# S7G2_footprint_with_caps_v1p1.net
KiCad netlist of a schematic drawn in EAGLE
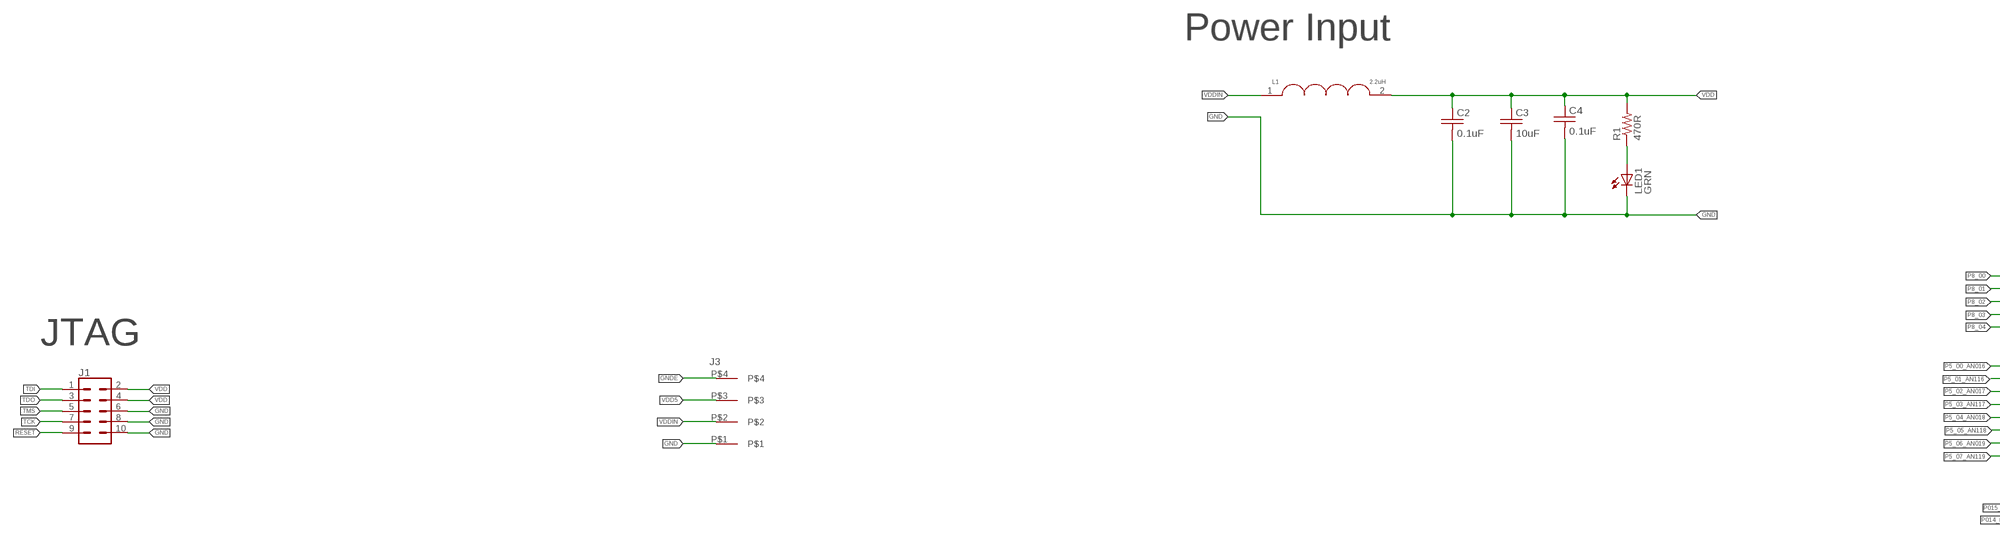
[diagram p0: schematic, sheet 1, part 1 of 3]
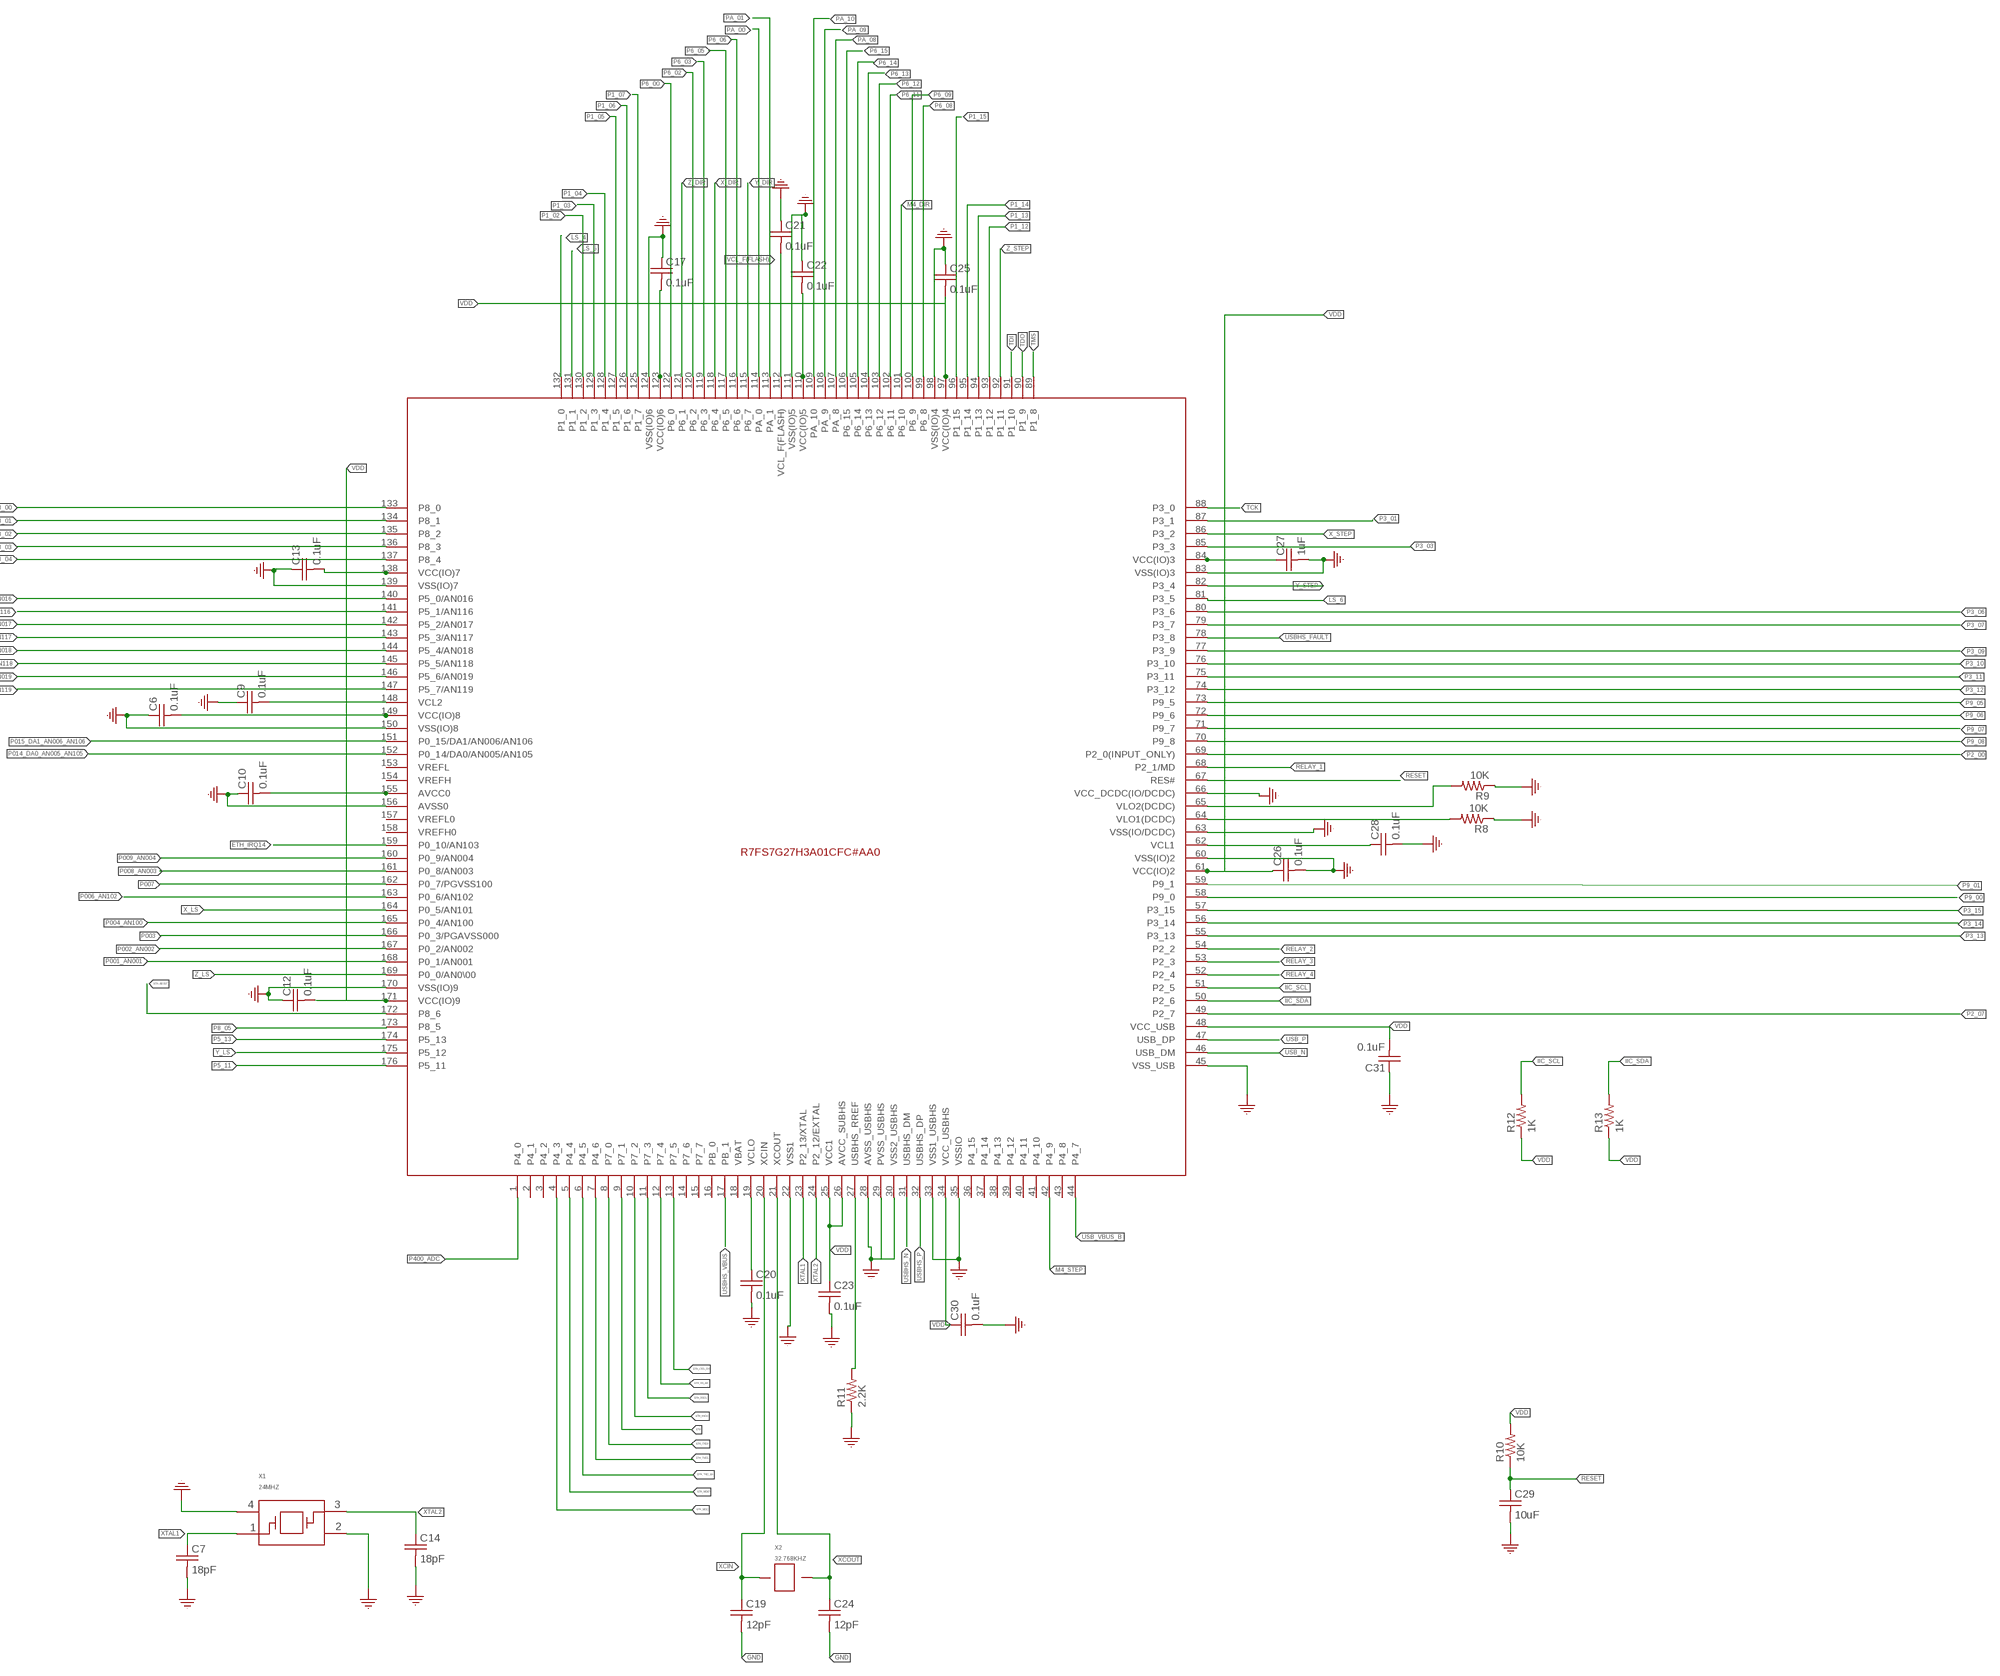
[diagram p1: schematic, sheet 1, part 2 of 3]
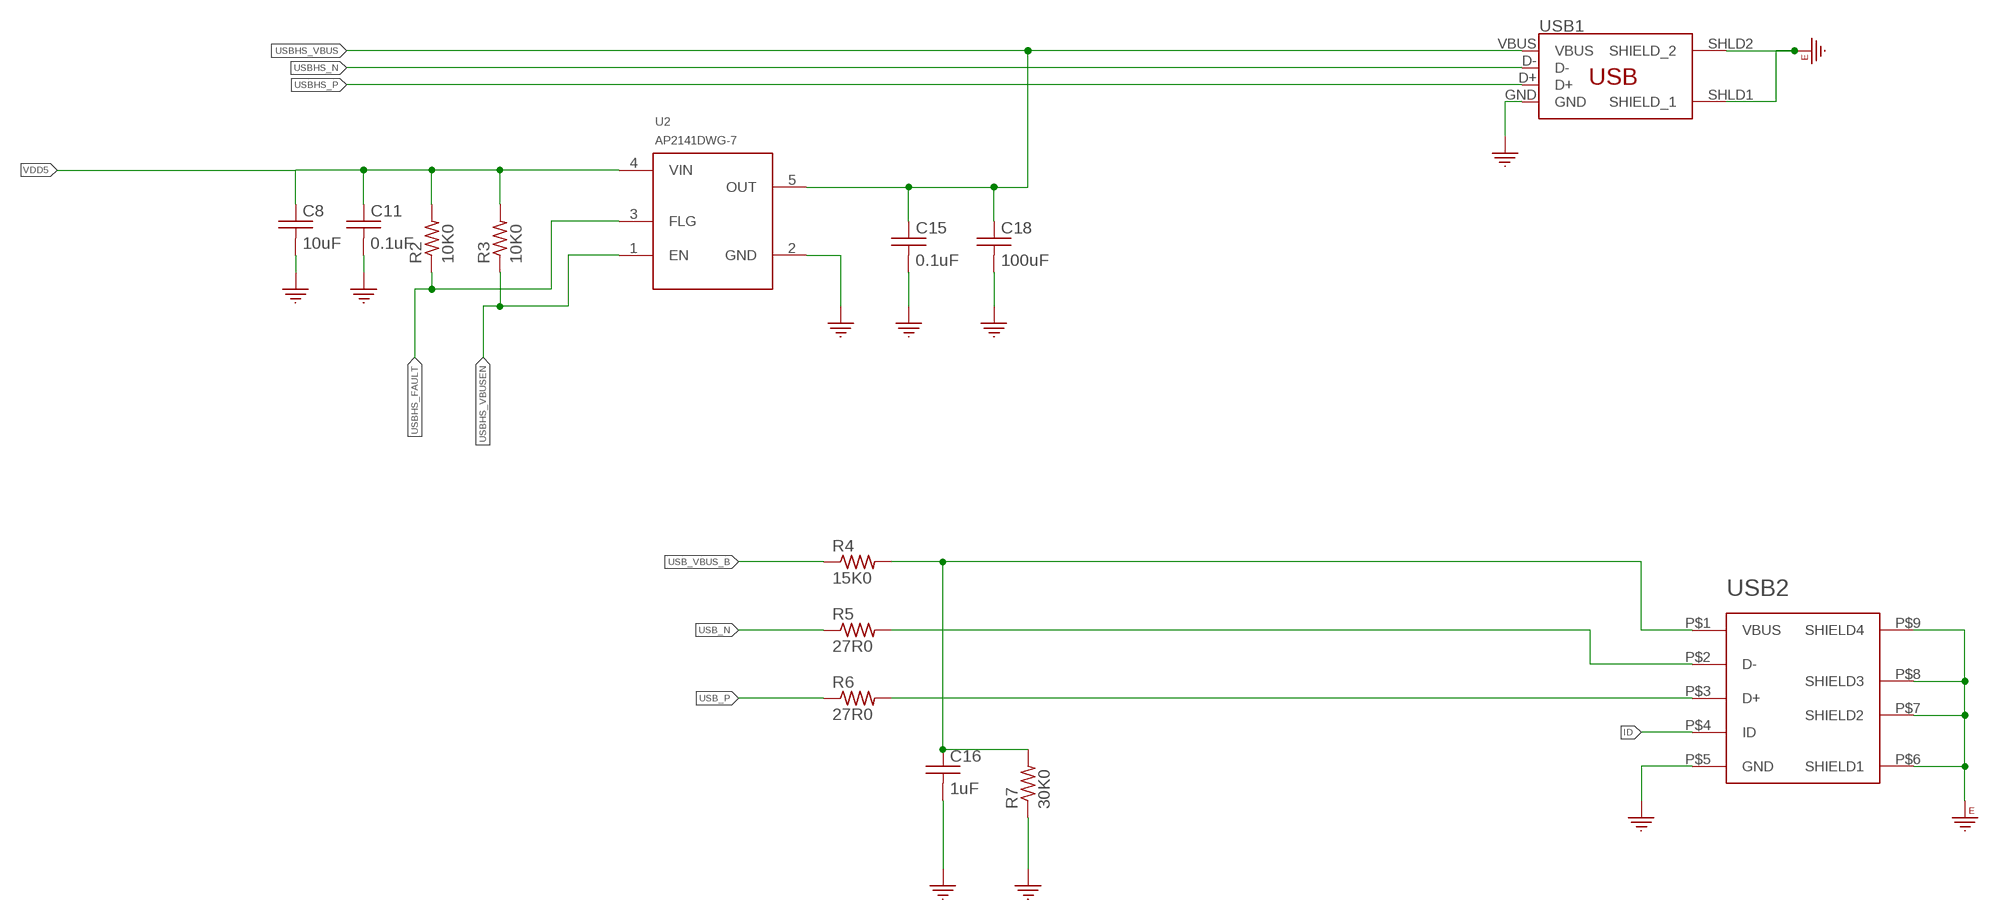
[diagram p2: schematic, sheet 1, part 3 of 3]

(export (version "E")
  (design (tool "Eeschema 10.0.6"))
  (components
    (comp (ref "C2")
      (value "0.1uF")
      (footprint "eagle-import:0402")
      (libsource (lib "eagle-import") (part "C_0402"))
    )
    (comp (ref "C3")
      (value "10uF")
      (footprint "eagle-import:0402")
      (libsource (lib "eagle-import") (part "C_0402"))
    )
    (comp (ref "C4")
      (value "0.1uF")
      (footprint "eagle-import:0402")
      (libsource (lib "eagle-import") (part "C_0402"))
    )
    (comp (ref "C6")
      (value "0.1uF")
      (footprint "eagle-import:0402")
      (libsource (lib "eagle-import") (part "C_0402"))
    )
    (comp (ref "C7")
      (value "18pF")
      (footprint "eagle-import:0402")
      (libsource (lib "eagle-import") (part "C_0402"))
    )
    (comp (ref "C8")
      (value "10uF")
      (footprint "eagle-import:0402")
      (libsource (lib "eagle-import") (part "C_0402"))
    )
    (comp (ref "C9")
      (value "0.1uF")
      (footprint "eagle-import:0402")
      (libsource (lib "eagle-import") (part "C_0402"))
    )
    (comp (ref "C10")
      (value "0.1uF")
      (footprint "eagle-import:0402")
      (libsource (lib "eagle-import") (part "C_0402"))
    )
    (comp (ref "C11")
      (value "0.1uF")
      (footprint "eagle-import:0402")
      (libsource (lib "eagle-import") (part "C_0402"))
    )
    (comp (ref "C12")
      (value "0.1uF")
      (footprint "eagle-import:0402")
      (libsource (lib "eagle-import") (part "C_0402"))
    )
    (comp (ref "C13")
      (value "0.1uF")
      (footprint "eagle-import:0402")
      (libsource (lib "eagle-import") (part "C_0402"))
    )
    (comp (ref "C14")
      (value "18pF")
      (footprint "eagle-import:0402")
      (libsource (lib "eagle-import") (part "C_0402"))
    )
    (comp (ref "C15")
      (value "0.1uF")
      (footprint "eagle-import:0402")
      (libsource (lib "eagle-import") (part "C_0402"))
    )
    (comp (ref "C16")
      (value "1uF")
      (footprint "eagle-import:0402")
      (libsource (lib "eagle-import") (part "C_0402"))
    )
    (comp (ref "C17")
      (value "0.1uF")
      (footprint "eagle-import:0402")
      (libsource (lib "eagle-import") (part "C_0402"))
    )
    (comp (ref "C18")
      (value "100uF")
      (footprint "eagle-import:C1210")
      (libsource (lib "eagle-import") (part "C_1210"))
    )
    (comp (ref "C19")
      (value "12pF")
      (footprint "eagle-import:0402")
      (libsource (lib "eagle-import") (part "C_0402"))
    )
    (comp (ref "C20")
      (value "0.1uF")
      (footprint "eagle-import:0402")
      (libsource (lib "eagle-import") (part "C_0402"))
    )
    (comp (ref "C21")
      (value "0.1uF")
      (footprint "eagle-import:0402")
      (libsource (lib "eagle-import") (part "C_0402"))
    )
    (comp (ref "C22")
      (value "0.1uF")
      (footprint "eagle-import:0402")
      (libsource (lib "eagle-import") (part "C_0402"))
    )
    (comp (ref "C23")
      (value "0.1uF")
      (footprint "eagle-import:0402")
      (libsource (lib "eagle-import") (part "C_0402"))
    )
    (comp (ref "C24")
      (value "12pF")
      (footprint "eagle-import:0402")
      (libsource (lib "eagle-import") (part "C_0402"))
    )
    (comp (ref "C25")
      (value "0.1uF")
      (footprint "eagle-import:0402")
      (libsource (lib "eagle-import") (part "C_0402"))
    )
    (comp (ref "C26")
      (value "0.1uF")
      (footprint "eagle-import:0402")
      (libsource (lib "eagle-import") (part "C_0402"))
    )
    (comp (ref "C27")
      (value "1uF")
      (footprint "eagle-import:0402")
      (libsource (lib "eagle-import") (part "C_0402"))
    )
    (comp (ref "C28")
      (value "0.1uF")
      (footprint "eagle-import:0402")
      (libsource (lib "eagle-import") (part "C_0402"))
    )
    (comp (ref "C29")
      (value "10uF")
      (footprint "eagle-import:0402")
      (libsource (lib "eagle-import") (part "C_0402"))
    )
    (comp (ref "C30")
      (value "0.1uF")
      (footprint "eagle-import:0402")
      (libsource (lib "eagle-import") (part "C_0402"))
    )
    (comp (ref "C31")
      (value "0.1uF")
      (footprint "eagle-import:0402")
      (libsource (lib "eagle-import") (part "C_0402"))
    )
    (comp (ref "J1")
      (value "CONN_05X2PTH")
      (footprint "eagle-import:2X5")
      (libsource (lib "eagle-import") (part "CONN_05X2PTH"))
    )
    (comp (ref "J3")
      (value "3.81MM_1_X_4_RT_ANGLE_PLUG_HEADER")
      (footprint "eagle-import:1X4_3.81MM_PITCH")
      (libsource (lib "eagle-import") (part "3.81MM_1_X_4_RT_ANGLE_PLUG_HEADER"))
    )
    (comp (ref "L1")
      (value "2.2uH")
      (footprint "eagle-import:1008_(2520_METRIC)")
      (libsource (lib "eagle-import") (part "INDUCTOR_1008_2.2_MH_1.3A"))
    )
    (comp (ref "LED1")
      (value "LED_0805_GREEN")
      (footprint "eagle-import:LED_0805_GREEN")
      (libsource (lib "eagle-import") (part "LED_0805_GREEN"))
    )
    (comp (ref "R1")
      (value "470R")
      (footprint "eagle-import:0402")
      (libsource (lib "eagle-import") (part "R_0402"))
    )
    (comp (ref "R2")
      (value "10K0")
      (footprint "eagle-import:0402")
      (libsource (lib "eagle-import") (part "R_0402"))
    )
    (comp (ref "R3")
      (value "10K0")
      (footprint "eagle-import:0402")
      (libsource (lib "eagle-import") (part "R_0402"))
    )
    (comp (ref "R4")
      (value "15K0")
      (footprint "eagle-import:0402")
      (libsource (lib "eagle-import") (part "R_0402"))
    )
    (comp (ref "R5")
      (value "27R0")
      (footprint "eagle-import:0402")
      (libsource (lib "eagle-import") (part "R_0402"))
    )
    (comp (ref "R6")
      (value "27R0")
      (footprint "eagle-import:0402")
      (libsource (lib "eagle-import") (part "R_0402"))
    )
    (comp (ref "R7")
      (value "30K0")
      (footprint "eagle-import:0402")
      (libsource (lib "eagle-import") (part "R_0402"))
    )
    (comp (ref "R8")
      (value "10K")
      (footprint "eagle-import:0402")
      (libsource (lib "eagle-import") (part "R_0402"))
    )
    (comp (ref "R9")
      (value "10K")
      (footprint "eagle-import:0402")
      (libsource (lib "eagle-import") (part "R_0402"))
    )
    (comp (ref "R10")
      (value "10K")
      (footprint "eagle-import:0402")
      (libsource (lib "eagle-import") (part "R_0402"))
    )
    (comp (ref "R11")
      (value "2.2K")
      (footprint "eagle-import:0402")
      (libsource (lib "eagle-import") (part "R_0402"))
    )
    (comp (ref "R12")
      (value "1K")
      (footprint "eagle-import:0402")
      (libsource (lib "eagle-import") (part "R_0402"))
    )
    (comp (ref "R13")
      (value "1K")
      (footprint "eagle-import:0402")
      (libsource (lib "eagle-import") (part "R_0402"))
    )
    (comp (ref "U2")
      (value "AP2141DWG-5")
      (footprint "eagle-import:SOT-23-5")
      (libsource (lib "eagle-import") (part "AP2141DWG-5"))
    )
    (comp (ref "U5")
      (value "S7G2_X_176")
      (footprint "eagle-import:LQFP176_24X24")
      (libsource (lib "eagle-import") (part "S7G2_X_176"))
    )
    (comp (ref "USB1")
      (value "USB_A")
      (footprint "eagle-import:USB_A_SMT")
      (libsource (lib "eagle-import") (part "USB_A"))
    )
    (comp (ref "USB2")
      (value "USB_MICRO-B")
      (footprint "eagle-import:USB_MICRO-B")
      (libsource (lib "eagle-import") (part "USB_MICRO-B"))
    )
    (comp (ref "X1")
      (value "24MHZ")
      (footprint "eagle-import:SMD_3225")
      (libsource (lib "eagle-import") (part "XTAL_24_MHZ"))
    )
    (comp (ref "X2")
      (value "32.768KHZ")
      (footprint "eagle-import:SMD_X_2_PADS")
      (libsource (lib "eagle-import") (part "XTAL_32.768KHZ"))
    )
  )
  (nets
    (net (code "1") (name "ETH") (class "Default")
      (node (ref "U5") (pin "9") (pinfunction "P7_1_9") (pintype "bidirectional"))
    )
    (net (code "2") (name "ETH_CRS_DV") (class "Default")
      (node (ref "U5") (pin "13") (pinfunction "P7_5_13") (pintype "bidirectional"))
    )
    (net (code "3") (name "ETH_IRQ14") (class "Default")
      (node (ref "U5") (pin "159") (pinfunction "P0_10/AN103_159") (pintype "bidirectional"))
    )
    (net (code "4") (name "ETH_MDC") (class "Default")
      (node (ref "U5") (pin "4") (pinfunction "P4_3_4") (pintype "bidirectional"))
    )
    (net (code "5") (name "ETH_MDIO") (class "Default")
      (node (ref "U5") (pin "5") (pinfunction "P4_4_5") (pintype "bidirectional"))
    )
    (net (code "6") (name "ETH_RESET") (class "Default")
      (node (ref "U5") (pin "172") (pinfunction "P8_6_172") (pintype "bidirectional"))
    )
    (net (code "7") (name "ETH_RXD0") (class "Default")
      (node (ref "U5") (pin "10") (pinfunction "P7_2_10") (pintype "bidirectional"))
    )
    (net (code "8") (name "ETH_RXD1") (class "Default")
      (node (ref "U5") (pin "11") (pinfunction "P7_3_11") (pintype "bidirectional"))
    )
    (net (code "9") (name "ETH_RX_ER") (class "Default")
      (node (ref "U5") (pin "12") (pinfunction "P7_4_12") (pintype "bidirectional"))
    )
    (net (code "10") (name "ETH_TXD0") (class "Default")
      (node (ref "U5") (pin "8") (pinfunction "P7_0_8") (pintype "bidirectional"))
    )
    (net (code "11") (name "ETH_TXD1") (class "Default")
      (node (ref "U5") (pin "7") (pinfunction "P4_6_7") (pintype "bidirectional"))
    )
    (net (code "12") (name "ETH_TXD_EN") (class "Default")
      (node (ref "U5") (pin "6") (pinfunction "P4_5_6") (pintype "bidirectional"))
    )
    (net (code "13") (name "GND") (class "Default")
      (node (ref "C10") (pin "P$1") (pinfunction "1_P$1") (pintype "passive"))
      (node (ref "C11") (pin "P$2") (pinfunction "2_P$2") (pintype "passive"))
      (node (ref "C12") (pin "P$1") (pinfunction "1_P$1") (pintype "passive"))
      (node (ref "C13") (pin "P$1") (pinfunction "1_P$1") (pintype "passive"))
      (node (ref "C14") (pin "P$2") (pinfunction "2_P$2") (pintype "passive"))
      (node (ref "C15") (pin "P$2") (pinfunction "2_P$2") (pintype "passive"))
      (node (ref "C16") (pin "P$2") (pinfunction "2_P$2") (pintype "passive"))
      (node (ref "C17") (pin "P$1") (pinfunction "1_P$1") (pintype "passive"))
      (node (ref "C18") (pin "2") (pinfunction "2_2") (pintype "passive"))
      (node (ref "C19") (pin "P$2") (pinfunction "2_P$2") (pintype "passive"))
      (node (ref "C2") (pin "P$2") (pinfunction "2_P$2") (pintype "passive"))
      (node (ref "C20") (pin "P$2") (pinfunction "2_P$2") (pintype "passive"))
      (node (ref "C21") (pin "P$1") (pinfunction "1_P$1") (pintype "passive"))
      (node (ref "C22") (pin "P$1") (pinfunction "1_P$1") (pintype "passive"))
      (node (ref "C23") (pin "P$2") (pinfunction "2_P$2") (pintype "passive"))
      (node (ref "C24") (pin "P$2") (pinfunction "2_P$2") (pintype "passive"))
      (node (ref "C25") (pin "P$1") (pinfunction "1_P$1") (pintype "passive"))
      (node (ref "C26") (pin "P$2") (pinfunction "2_P$2") (pintype "passive"))
      (node (ref "C27") (pin "P$2") (pinfunction "2_P$2") (pintype "passive"))
      (node (ref "C28") (pin "P$2") (pinfunction "2_P$2") (pintype "passive"))
      (node (ref "C29") (pin "P$2") (pinfunction "2_P$2") (pintype "passive"))
      (node (ref "C3") (pin "P$2") (pinfunction "2_P$2") (pintype "passive"))
      (node (ref "C30") (pin "P$2") (pinfunction "2_P$2") (pintype "passive"))
      (node (ref "C31") (pin "P$1") (pinfunction "1_P$1") (pintype "passive"))
      (node (ref "C4") (pin "P$2") (pinfunction "2_P$2") (pintype "passive"))
      (node (ref "C6") (pin "P$1") (pinfunction "1_P$1") (pintype "passive"))
      (node (ref "C7") (pin "P$2") (pinfunction "2_P$2") (pintype "passive"))
      (node (ref "C8") (pin "P$2") (pinfunction "2_P$2") (pintype "passive"))
      (node (ref "C9") (pin "P$1") (pinfunction "1_P$1") (pintype "passive"))
      (node (ref "J1") (pin "10") (pinfunction "10_10") (pintype "passive"))
      (node (ref "J1") (pin "6") (pinfunction "6_6") (pintype "passive"))
      (node (ref "J1") (pin "8") (pinfunction "8_8") (pintype "passive"))
      (node (ref "J3") (pin "P$1") (pinfunction "P$1_P$1") (pintype "bidirectional"))
      (node (ref "LED1") (pin "C") (pinfunction "C_C") (pintype "passive"))
      (node (ref "R11") (pin "P$1") (pinfunction "1_P$1") (pintype "passive"))
      (node (ref "R7") (pin "P$1") (pinfunction "1_P$1") (pintype "passive"))
      (node (ref "R8") (pin "P$1") (pinfunction "1_P$1") (pintype "passive"))
      (node (ref "R9") (pin "P$1") (pinfunction "1_P$1") (pintype "passive"))
      (node (ref "U2") (pin "2") (pinfunction "GND_2") (pintype "input"))
      (node (ref "U5") (pin "111") (pinfunction "VSS(IO)5_111") (pintype "bidirectional"))
      (node (ref "U5") (pin "124") (pinfunction "VSS(IO)6_124") (pintype "bidirectional"))
      (node (ref "U5") (pin "139") (pinfunction "VSS(IO)7_139") (pintype "bidirectional"))
      (node (ref "U5") (pin "150") (pinfunction "VSS(IO)8_150") (pintype "bidirectional"))
      (node (ref "U5") (pin "156") (pinfunction "AVSS0_156") (pintype "bidirectional"))
      (node (ref "U5") (pin "170") (pinfunction "VSS(IO)9_170") (pintype "bidirectional"))
      (node (ref "U5") (pin "22") (pinfunction "VSS1_22") (pintype "bidirectional"))
      (node (ref "U5") (pin "28") (pinfunction "AVSS_USBHS_28") (pintype "bidirectional"))
      (node (ref "U5") (pin "29") (pinfunction "PVSS_USBHS_29") (pintype "bidirectional"))
      (node (ref "U5") (pin "30") (pinfunction "VSS2_USBHS_30") (pintype "bidirectional"))
      (node (ref "U5") (pin "33") (pinfunction "VSS1_USBHS_33") (pintype "bidirectional"))
      (node (ref "U5") (pin "35") (pinfunction "VSSIO_35") (pintype "bidirectional"))
      (node (ref "U5") (pin "45") (pinfunction "VSS_USB_45") (pintype "bidirectional"))
      (node (ref "U5") (pin "60") (pinfunction "VSS(IO)2_60") (pintype "bidirectional"))
      (node (ref "U5") (pin "63") (pinfunction "VSS(IO/DCDC)_63") (pintype "bidirectional"))
      (node (ref "U5") (pin "66") (pinfunction "VCC_DCDC(IO/DCDC)_66") (pintype "bidirectional"))
      (node (ref "U5") (pin "83") (pinfunction "VSS(IO)3_83") (pintype "bidirectional"))
      (node (ref "U5") (pin "98") (pinfunction "VSS(IO)4_98") (pintype "bidirectional"))
      (node (ref "USB1") (pin "GND") (pinfunction "GND_GND") (pintype "power_in"))
      (node (ref "USB2") (pin "P$5") (pinfunction "GND_P$5") (pintype "bidirectional"))
      (node (ref "X1") (pin "2") (pinfunction "2_2") (pintype "bidirectional"))
      (node (ref "X1") (pin "4") (pinfunction "4_4") (pintype "bidirectional"))
    )
    (net (code "14") (name "GNDE") (class "Default")
      (node (ref "J3") (pin "P$4") (pinfunction "P$4_P$4") (pintype "bidirectional"))
      (node (ref "USB1") (pin "SHLD1") (pinfunction "SHIELD_1_SHLD1") (pintype "bidirectional"))
      (node (ref "USB1") (pin "SHLD2") (pinfunction "SHIELD_2_SHLD2") (pintype "bidirectional"))
      (node (ref "USB2") (pin "P$6") (pinfunction "SHIELD1_P$6") (pintype "bidirectional"))
      (node (ref "USB2") (pin "P$7") (pinfunction "SHIELD2_P$7") (pintype "bidirectional"))
      (node (ref "USB2") (pin "P$8") (pinfunction "SHIELD3_P$8") (pintype "bidirectional"))
      (node (ref "USB2") (pin "P$9") (pinfunction "SHIELD4_P$9") (pintype "bidirectional"))
    )
    (net (code "15") (name "ID") (class "Default")
      (node (ref "USB2") (pin "P$4") (pinfunction "ID_P$4") (pintype "bidirectional"))
    )
    (net (code "16") (name "IIC_SCL") (class "Default")
      (node (ref "R12") (pin "P$2") (pinfunction "2_P$2") (pintype "passive"))
      (node (ref "U5") (pin "51") (pinfunction "P2_5_51") (pintype "bidirectional"))
    )
    (net (code "17") (name "IIC_SDA") (class "Default")
      (node (ref "R13") (pin "P$2") (pinfunction "2_P$2") (pintype "passive"))
      (node (ref "U5") (pin "50") (pinfunction "P2_6_50") (pintype "bidirectional"))
    )
    (net (code "18") (name "LS_4") (class "Default")
      (node (ref "U5") (pin "132") (pinfunction "P1_0_132") (pintype "bidirectional"))
    )
    (net (code "19") (name "LS_5") (class "Default")
      (node (ref "U5") (pin "131") (pinfunction "P1_1_131") (pintype "bidirectional"))
    )
    (net (code "20") (name "LS_6") (class "Default")
      (node (ref "U5") (pin "81") (pinfunction "P3_5_81") (pintype "bidirectional"))
    )
    (net (code "21") (name "M4_DIR") (class "Default")
      (node (ref "U5") (pin "101") (pinfunction "P6_10_101") (pintype "bidirectional"))
    )
    (net (code "22") (name "M4_STEP") (class "Default")
      (node (ref "U5") (pin "42") (pinfunction "P4_9_42") (pintype "bidirectional"))
    )
    (net (code "23") (name "Net-(C9-2)") (class "Default")
      (node (ref "C9") (pin "P$2") (pinfunction "2_P$2") (pintype "passive"))
      (node (ref "U5") (pin "148") (pinfunction "VCL2_148") (pintype "bidirectional"))
    )
    (net (code "24") (name "Net-(C16-1)") (class "Default")
      (node (ref "C16") (pin "P$1") (pinfunction "1_P$1") (pintype "passive"))
      (node (ref "R4") (pin "P$2") (pinfunction "2_P$2") (pintype "passive"))
      (node (ref "R7") (pin "P$2") (pinfunction "2_P$2") (pintype "passive"))
      (node (ref "USB2") (pin "P$1") (pinfunction "VBUS_P$1") (pintype "bidirectional"))
    )
    (net (code "25") (name "Net-(C20-1)") (class "Default")
      (node (ref "C20") (pin "P$1") (pinfunction "1_P$1") (pintype "passive"))
      (node (ref "U5") (pin "19") (pinfunction "VCLO_19") (pintype "bidirectional"))
    )
    (net (code "26") (name "Net-(C28-1)") (class "Default")
      (node (ref "C28") (pin "P$1") (pinfunction "1_P$1") (pintype "passive"))
      (node (ref "U5") (pin "62") (pinfunction "VCL1_62") (pintype "bidirectional"))
    )
    (net (code "27") (name "Net-(R1-1)") (class "Default")
      (node (ref "LED1") (pin "A") (pinfunction "A_A") (pintype "passive"))
      (node (ref "R1") (pin "P$1") (pinfunction "1_P$1") (pintype "passive"))
    )
    (net (code "28") (name "Net-(R5-2)") (class "Default")
      (node (ref "R5") (pin "P$2") (pinfunction "2_P$2") (pintype "passive"))
      (node (ref "USB2") (pin "P$2") (pinfunction "D-_P$2") (pintype "bidirectional"))
    )
    (net (code "29") (name "Net-(R6-2)") (class "Default")
      (node (ref "R6") (pin "P$2") (pinfunction "2_P$2") (pintype "passive"))
      (node (ref "USB2") (pin "P$3") (pinfunction "D+_P$3") (pintype "bidirectional"))
    )
    (net (code "30") (name "Net-(R8-2)") (class "Default")
      (node (ref "R8") (pin "P$2") (pinfunction "2_P$2") (pintype "passive"))
      (node (ref "U5") (pin "64") (pinfunction "VLO1(DCDC)_64") (pintype "bidirectional"))
    )
    (net (code "31") (name "Net-(R9-2)") (class "Default")
      (node (ref "R9") (pin "P$2") (pinfunction "2_P$2") (pintype "passive"))
      (node (ref "U5") (pin "65") (pinfunction "VLO2(DCDC)_65") (pintype "bidirectional"))
    )
    (net (code "32") (name "Net-(R11-2)") (class "Default")
      (node (ref "R11") (pin "P$2") (pinfunction "2_P$2") (pintype "passive"))
      (node (ref "U5") (pin "27") (pinfunction "USBHS_RREF_27") (pintype "bidirectional"))
    )
    (net (code "33") (name "P1_02") (class "Default")
      (node (ref "U5") (pin "130") (pinfunction "P1_2_130") (pintype "bidirectional"))
    )
    (net (code "34") (name "P1_03") (class "Default")
      (node (ref "U5") (pin "129") (pinfunction "P1_3_129") (pintype "bidirectional"))
    )
    (net (code "35") (name "P1_04") (class "Default")
      (node (ref "U5") (pin "128") (pinfunction "P1_4_128") (pintype "bidirectional"))
    )
    (net (code "36") (name "P1_05") (class "Default")
      (node (ref "U5") (pin "127") (pinfunction "P1_5_127") (pintype "bidirectional"))
    )
    (net (code "37") (name "P1_06") (class "Default")
      (node (ref "U5") (pin "126") (pinfunction "P1_6_126") (pintype "bidirectional"))
    )
    (net (code "38") (name "P1_07") (class "Default")
      (node (ref "U5") (pin "125") (pinfunction "P1_7_125") (pintype "bidirectional"))
    )
    (net (code "39") (name "P1_12") (class "Default")
      (node (ref "U5") (pin "93") (pinfunction "P1_12_93") (pintype "bidirectional"))
    )
    (net (code "40") (name "P1_13") (class "Default")
      (node (ref "U5") (pin "94") (pinfunction "P1_13_94") (pintype "bidirectional"))
    )
    (net (code "41") (name "P1_14") (class "Default")
      (node (ref "U5") (pin "95") (pinfunction "P1_14_95") (pintype "bidirectional"))
    )
    (net (code "42") (name "P1_15") (class "Default")
      (node (ref "U5") (pin "96") (pinfunction "P1_15_96") (pintype "bidirectional"))
    )
    (net (code "43") (name "P001_AN001") (class "Default")
      (node (ref "U5") (pin "168") (pinfunction "P0_1/AN001_168") (pintype "bidirectional"))
    )
    (net (code "44") (name "P2_00") (class "Default")
      (node (ref "U5") (pin "69") (pinfunction "P2_0(INPUT_ONLY)_69") (pintype "bidirectional"))
    )
    (net (code "45") (name "P2_07") (class "Default")
      (node (ref "U5") (pin "49") (pinfunction "P2_7_49") (pintype "bidirectional"))
    )
    (net (code "46") (name "P002_AN002") (class "Default")
      (node (ref "U5") (pin "167") (pinfunction "P0_2/AN002_167") (pintype "bidirectional"))
    )
    (net (code "47") (name "P003") (class "Default")
      (node (ref "U5") (pin "166") (pinfunction "P0_3/PGAVSS000_166") (pintype "bidirectional"))
    )
    (net (code "48") (name "P3_01") (class "Default")
      (node (ref "U5") (pin "87") (pinfunction "P3_1_87") (pintype "bidirectional"))
    )
    (net (code "49") (name "P3_03") (class "Default")
      (node (ref "U5") (pin "85") (pinfunction "P3_3_85") (pintype "bidirectional"))
    )
    (net (code "50") (name "P3_06") (class "Default")
      (node (ref "U5") (pin "80") (pinfunction "P3_6_80") (pintype "bidirectional"))
    )
    (net (code "51") (name "P3_07") (class "Default")
      (node (ref "U5") (pin "79") (pinfunction "P3_7_79") (pintype "bidirectional"))
    )
    (net (code "52") (name "P3_09") (class "Default")
      (node (ref "U5") (pin "77") (pinfunction "P3_9_77") (pintype "bidirectional"))
    )
    (net (code "53") (name "P3_10") (class "Default")
      (node (ref "U5") (pin "76") (pinfunction "P3_10_76") (pintype "bidirectional"))
    )
    (net (code "54") (name "P3_11") (class "Default")
      (node (ref "U5") (pin "75") (pinfunction "P3_11_75") (pintype "bidirectional"))
    )
    (net (code "55") (name "P3_12") (class "Default")
      (node (ref "U5") (pin "74") (pinfunction "P3_12_74") (pintype "bidirectional"))
    )
    (net (code "56") (name "P3_13") (class "Default")
      (node (ref "U5") (pin "55") (pinfunction "P3_13_55") (pintype "bidirectional"))
    )
    (net (code "57") (name "P3_14") (class "Default")
      (node (ref "U5") (pin "56") (pinfunction "P3_14_56") (pintype "bidirectional"))
    )
    (net (code "58") (name "P3_15") (class "Default")
      (node (ref "U5") (pin "57") (pinfunction "P3_15_57") (pintype "bidirectional"))
    )
    (net (code "59") (name "P004_AN100") (class "Default")
      (node (ref "U5") (pin "165") (pinfunction "P0_4/AN100_165") (pintype "bidirectional"))
    )
    (net (code "60") (name "P5_00_AN016") (class "Default")
      (node (ref "U5") (pin "140") (pinfunction "P5_0/AN016_140") (pintype "bidirectional"))
    )
    (net (code "61") (name "P5_01_AN116") (class "Default")
      (node (ref "U5") (pin "141") (pinfunction "P5_1/AN116_141") (pintype "bidirectional"))
    )
    (net (code "62") (name "P5_02_AN017") (class "Default")
      (node (ref "U5") (pin "142") (pinfunction "P5_2/AN017_142") (pintype "bidirectional"))
    )
    (net (code "63") (name "P5_03_AN117") (class "Default")
      (node (ref "U5") (pin "143") (pinfunction "P5_3/AN117_143") (pintype "bidirectional"))
    )
    (net (code "64") (name "P5_04_AN018") (class "Default")
      (node (ref "U5") (pin "144") (pinfunction "P5_4/AN018_144") (pintype "bidirectional"))
    )
    (net (code "65") (name "P5_05_AN118") (class "Default")
      (node (ref "U5") (pin "145") (pinfunction "P5_5/AN118_145") (pintype "bidirectional"))
    )
    (net (code "66") (name "P5_06_AN019") (class "Default")
      (node (ref "U5") (pin "146") (pinfunction "P5_6/AN019_146") (pintype "bidirectional"))
    )
    (net (code "67") (name "P5_07_AN119") (class "Default")
      (node (ref "U5") (pin "147") (pinfunction "P5_7/AN119_147") (pintype "bidirectional"))
    )
    (net (code "68") (name "P5_11") (class "Default")
      (node (ref "U5") (pin "176") (pinfunction "P5_11_176") (pintype "bidirectional"))
    )
    (net (code "69") (name "P5_13") (class "Default")
      (node (ref "U5") (pin "174") (pinfunction "P5_13_174") (pintype "bidirectional"))
    )
    (net (code "70") (name "P6_00") (class "Default")
      (node (ref "U5") (pin "122") (pinfunction "P6_0_122") (pintype "bidirectional"))
    )
    (net (code "71") (name "P6_02") (class "Default")
      (node (ref "U5") (pin "120") (pinfunction "P6_2_120") (pintype "bidirectional"))
    )
    (net (code "72") (name "P6_03") (class "Default")
      (node (ref "U5") (pin "119") (pinfunction "P6_3_119") (pintype "bidirectional"))
    )
    (net (code "73") (name "P6_05") (class "Default")
      (node (ref "U5") (pin "117") (pinfunction "P6_5_117") (pintype "bidirectional"))
    )
    (net (code "74") (name "P6_06") (class "Default")
      (node (ref "U5") (pin "116") (pinfunction "P6_6_116") (pintype "bidirectional"))
    )
    (net (code "75") (name "P6_08") (class "Default")
      (node (ref "U5") (pin "99") (pinfunction "P6_8_99") (pintype "bidirectional"))
    )
    (net (code "76") (name "P6_09") (class "Default")
      (node (ref "U5") (pin "100") (pinfunction "P6_9_100") (pintype "bidirectional"))
    )
    (net (code "77") (name "P6_11") (class "Default")
      (node (ref "U5") (pin "102") (pinfunction "P6_11_102") (pintype "bidirectional"))
    )
    (net (code "78") (name "P6_12") (class "Default")
      (node (ref "U5") (pin "103") (pinfunction "P6_12_103") (pintype "bidirectional"))
    )
    (net (code "79") (name "P6_13") (class "Default")
      (node (ref "U5") (pin "104") (pinfunction "P6_13_104") (pintype "bidirectional"))
    )
    (net (code "80") (name "P6_14") (class "Default")
      (node (ref "U5") (pin "105") (pinfunction "P6_14_105") (pintype "bidirectional"))
    )
    (net (code "81") (name "P6_15") (class "Default")
      (node (ref "U5") (pin "106") (pinfunction "P6_15_106") (pintype "bidirectional"))
    )
    (net (code "82") (name "P006_AN102") (class "Default")
      (node (ref "U5") (pin "163") (pinfunction "P0_6/AN102_163") (pintype "bidirectional"))
    )
    (net (code "83") (name "P007") (class "Default")
      (node (ref "U5") (pin "162") (pinfunction "P0_7/PGVSS100_162") (pintype "bidirectional"))
    )
    (net (code "84") (name "P8_00") (class "Default")
      (node (ref "U5") (pin "133") (pinfunction "P8_0_133") (pintype "bidirectional"))
    )
    (net (code "85") (name "P8_01") (class "Default")
      (node (ref "U5") (pin "134") (pinfunction "P8_1_134") (pintype "bidirectional"))
    )
    (net (code "86") (name "P8_02") (class "Default")
      (node (ref "U5") (pin "135") (pinfunction "P8_2_135") (pintype "bidirectional"))
    )
    (net (code "87") (name "P8_03") (class "Default")
      (node (ref "U5") (pin "136") (pinfunction "P8_3_136") (pintype "bidirectional"))
    )
    (net (code "88") (name "P8_04") (class "Default")
      (node (ref "U5") (pin "137") (pinfunction "P8_4_137") (pintype "bidirectional"))
    )
    (net (code "89") (name "P8_05") (class "Default")
      (node (ref "U5") (pin "173") (pinfunction "P8_5_173") (pintype "bidirectional"))
    )
    (net (code "90") (name "P008_AN003") (class "Default")
      (node (ref "U5") (pin "161") (pinfunction "P0_8/AN003_161") (pintype "bidirectional"))
    )
    (net (code "91") (name "P9_00") (class "Default")
      (node (ref "U5") (pin "58") (pinfunction "P9_0_58") (pintype "bidirectional"))
    )
    (net (code "92") (name "P9_01") (class "Default")
      (node (ref "U5") (pin "59") (pinfunction "P9_1_59") (pintype "bidirectional"))
    )
    (net (code "93") (name "P9_05") (class "Default")
      (node (ref "U5") (pin "73") (pinfunction "P9_5_73") (pintype "bidirectional"))
    )
    (net (code "94") (name "P9_06") (class "Default")
      (node (ref "U5") (pin "72") (pinfunction "P9_6_72") (pintype "bidirectional"))
    )
    (net (code "95") (name "P9_07") (class "Default")
      (node (ref "U5") (pin "71") (pinfunction "P9_7_71") (pintype "bidirectional"))
    )
    (net (code "96") (name "P9_08") (class "Default")
      (node (ref "U5") (pin "70") (pinfunction "P9_8_70") (pintype "bidirectional"))
    )
    (net (code "97") (name "P009_AN004") (class "Default")
      (node (ref "U5") (pin "160") (pinfunction "P0_9/AN004_160") (pintype "bidirectional"))
    )
    (net (code "98") (name "P014_DA0_AN005_AN105") (class "Default")
      (node (ref "U5") (pin "152") (pinfunction "P0_14/DA0/AN005/AN105_152") (pintype "bidirectional"))
    )
    (net (code "99") (name "P015_DA1_AN006_AN106") (class "Default")
      (node (ref "U5") (pin "151") (pinfunction "P0_15/DA1/AN006/AN106_151") (pintype "bidirectional"))
    )
    (net (code "100") (name "P400_ADC") (class "Default")
      (node (ref "U5") (pin "1") (pinfunction "P4_0_1") (pintype "bidirectional"))
    )
    (net (code "101") (name "PA_00") (class "Default")
      (node (ref "U5") (pin "114") (pinfunction "PA_0_114") (pintype "bidirectional"))
    )
    (net (code "102") (name "PA_01") (class "Default")
      (node (ref "U5") (pin "113") (pinfunction "PA_1_113") (pintype "bidirectional"))
    )
    (net (code "103") (name "PA_08") (class "Default")
      (node (ref "U5") (pin "107") (pinfunction "PA_8_107") (pintype "bidirectional"))
    )
    (net (code "104") (name "PA_09") (class "Default")
      (node (ref "U5") (pin "108") (pinfunction "PA_9_108") (pintype "bidirectional"))
    )
    (net (code "105") (name "PA_10") (class "Default")
      (node (ref "U5") (pin "109") (pinfunction "PA_10_109") (pintype "bidirectional"))
    )
    (net (code "106") (name "RELAY_1") (class "Default")
      (node (ref "U5") (pin "68") (pinfunction "P2_1/MD_68") (pintype "bidirectional"))
    )
    (net (code "107") (name "RELAY_2") (class "Default")
      (node (ref "U5") (pin "54") (pinfunction "P2_2_54") (pintype "bidirectional"))
    )
    (net (code "108") (name "RELAY_3") (class "Default")
      (node (ref "U5") (pin "53") (pinfunction "P2_3_53") (pintype "bidirectional"))
    )
    (net (code "109") (name "RELAY_4") (class "Default")
      (node (ref "U5") (pin "52") (pinfunction "P2_4_52") (pintype "bidirectional"))
    )
    (net (code "110") (name "RESET") (class "Default")
      (node (ref "C29") (pin "P$1") (pinfunction "1_P$1") (pintype "passive"))
      (node (ref "J1") (pin "9") (pinfunction "9_9") (pintype "passive"))
      (node (ref "R10") (pin "P$1") (pinfunction "1_P$1") (pintype "passive"))
      (node (ref "U5") (pin "67") (pinfunction "RES#_67") (pintype "bidirectional"))
    )
    (net (code "111") (name "TCK") (class "Default")
      (node (ref "J1") (pin "7") (pinfunction "7_7") (pintype "passive"))
      (node (ref "U5") (pin "88") (pinfunction "P3_0_88") (pintype "bidirectional"))
    )
    (net (code "112") (name "TDI") (class "Default")
      (node (ref "J1") (pin "1") (pinfunction "1_1") (pintype "passive"))
      (node (ref "U5") (pin "91") (pinfunction "P1_10_91") (pintype "bidirectional"))
    )
    (net (code "113") (name "TDO") (class "Default")
      (node (ref "J1") (pin "3") (pinfunction "3_3") (pintype "passive"))
      (node (ref "U5") (pin "90") (pinfunction "P1_9_90") (pintype "bidirectional"))
    )
    (net (code "114") (name "TMS") (class "Default")
      (node (ref "J1") (pin "5") (pinfunction "5_5") (pintype "passive"))
      (node (ref "U5") (pin "89") (pinfunction "P1_8_89") (pintype "bidirectional"))
    )
    (net (code "115") (name "USBHS_FAULT") (class "Default")
      (node (ref "R2") (pin "P$1") (pinfunction "1_P$1") (pintype "passive"))
      (node (ref "U2") (pin "3") (pinfunction "FLG_3") (pintype "input"))
      (node (ref "U5") (pin "78") (pinfunction "P3_8_78") (pintype "bidirectional"))
    )
    (net (code "116") (name "USBHS_N") (class "Default")
      (node (ref "U5") (pin "31") (pinfunction "USBHS_DM_31") (pintype "bidirectional"))
      (node (ref "USB1") (pin "D-") (pinfunction "D-_D-") (pintype "bidirectional"))
    )
    (net (code "117") (name "USBHS_P") (class "Default")
      (node (ref "U5") (pin "32") (pinfunction "USBHS_DP_32") (pintype "bidirectional"))
      (node (ref "USB1") (pin "D+") (pinfunction "D+_D+") (pintype "bidirectional"))
    )
    (net (code "118") (name "USBHS_VBUS") (class "Default")
      (node (ref "C15") (pin "P$1") (pinfunction "1_P$1") (pintype "passive"))
      (node (ref "C18") (pin "1") (pinfunction "1_1") (pintype "passive"))
      (node (ref "U2") (pin "5") (pinfunction "OUT_5") (pintype "input"))
      (node (ref "U5") (pin "17") (pinfunction "PB_1_17") (pintype "bidirectional"))
      (node (ref "USB1") (pin "VBUS") (pinfunction "VBUS_VBUS") (pintype "power_in"))
    )
    (net (code "119") (name "USBHS_VBUSEN") (class "Default")
      (node (ref "R3") (pin "P$1") (pinfunction "1_P$1") (pintype "passive"))
      (node (ref "U2") (pin "1") (pinfunction "EN_1") (pintype "input"))
    )
    (net (code "120") (name "USB_N") (class "Default")
      (node (ref "R5") (pin "P$1") (pinfunction "1_P$1") (pintype "passive"))
      (node (ref "U5") (pin "46") (pinfunction "USB_DM_46") (pintype "bidirectional"))
    )
    (net (code "121") (name "USB_P") (class "Default")
      (node (ref "R6") (pin "P$1") (pinfunction "1_P$1") (pintype "passive"))
      (node (ref "U5") (pin "47") (pinfunction "USB_DP_47") (pintype "bidirectional"))
    )
    (net (code "122") (name "USB_VBUS_B") (class "Default")
      (node (ref "R4") (pin "P$1") (pinfunction "1_P$1") (pintype "passive"))
      (node (ref "U5") (pin "44") (pinfunction "P4_7_44") (pintype "bidirectional"))
    )
    (net (code "123") (name "VCL_F(FLASH)") (class "Default")
      (node (ref "C21") (pin "P$2") (pinfunction "2_P$2") (pintype "passive"))
      (node (ref "U5") (pin "112") (pinfunction "VCL_F(FLASH)_112") (pintype "bidirectional"))
    )
    (net (code "124") (name "VDD") (class "Default")
      (node (ref "C10") (pin "P$2") (pinfunction "2_P$2") (pintype "passive"))
      (node (ref "C12") (pin "P$2") (pinfunction "2_P$2") (pintype "passive"))
      (node (ref "C13") (pin "P$2") (pinfunction "2_P$2") (pintype "passive"))
      (node (ref "C17") (pin "P$2") (pinfunction "2_P$2") (pintype "passive"))
      (node (ref "C2") (pin "P$1") (pinfunction "1_P$1") (pintype "passive"))
      (node (ref "C22") (pin "P$2") (pinfunction "2_P$2") (pintype "passive"))
      (node (ref "C23") (pin "P$1") (pinfunction "1_P$1") (pintype "passive"))
      (node (ref "C25") (pin "P$2") (pinfunction "2_P$2") (pintype "passive"))
      (node (ref "C26") (pin "P$1") (pinfunction "1_P$1") (pintype "passive"))
      (node (ref "C27") (pin "P$1") (pinfunction "1_P$1") (pintype "passive"))
      (node (ref "C3") (pin "P$1") (pinfunction "1_P$1") (pintype "passive"))
      (node (ref "C30") (pin "P$1") (pinfunction "1_P$1") (pintype "passive"))
      (node (ref "C31") (pin "P$2") (pinfunction "2_P$2") (pintype "passive"))
      (node (ref "C4") (pin "P$1") (pinfunction "1_P$1") (pintype "passive"))
      (node (ref "C6") (pin "P$2") (pinfunction "2_P$2") (pintype "passive"))
      (node (ref "J1") (pin "2") (pinfunction "2_2") (pintype "passive"))
      (node (ref "J1") (pin "4") (pinfunction "4_4") (pintype "passive"))
      (node (ref "L1") (pin "2") (pinfunction "P$2_2") (pintype "bidirectional"))
      (node (ref "R1") (pin "P$2") (pinfunction "2_P$2") (pintype "passive"))
      (node (ref "R10") (pin "P$2") (pinfunction "2_P$2") (pintype "passive"))
      (node (ref "R12") (pin "P$1") (pinfunction "1_P$1") (pintype "passive"))
      (node (ref "R13") (pin "P$1") (pinfunction "1_P$1") (pintype "passive"))
      (node (ref "U5") (pin "110") (pinfunction "VCC(IO)5_110") (pintype "bidirectional"))
      (node (ref "U5") (pin "123") (pinfunction "VCC(IO)6_123") (pintype "bidirectional"))
      (node (ref "U5") (pin "138") (pinfunction "VCC(IO)7_138") (pintype "bidirectional"))
      (node (ref "U5") (pin "149") (pinfunction "VCC(IO)8_149") (pintype "bidirectional"))
      (node (ref "U5") (pin "155") (pinfunction "AVCC0_155") (pintype "bidirectional"))
      (node (ref "U5") (pin "171") (pinfunction "VCC(IO)9_171") (pintype "bidirectional"))
      (node (ref "U5") (pin "25") (pinfunction "VCC1_25") (pintype "bidirectional"))
      (node (ref "U5") (pin "26") (pinfunction "AVCC_SUBHS_26") (pintype "bidirectional"))
      (node (ref "U5") (pin "34") (pinfunction "VCC_USBHS_34") (pintype "bidirectional"))
      (node (ref "U5") (pin "48") (pinfunction "VCC_USB_48") (pintype "bidirectional"))
      (node (ref "U5") (pin "61") (pinfunction "VCC(IO)2_61") (pintype "bidirectional"))
      (node (ref "U5") (pin "84") (pinfunction "VCC(IO)3_84") (pintype "bidirectional"))
      (node (ref "U5") (pin "97") (pinfunction "VCC(IO)4_97") (pintype "bidirectional"))
    )
    (net (code "125") (name "VDD5") (class "Default")
      (node (ref "C11") (pin "P$1") (pinfunction "1_P$1") (pintype "passive"))
      (node (ref "C8") (pin "P$1") (pinfunction "1_P$1") (pintype "passive"))
      (node (ref "J3") (pin "P$3") (pinfunction "P$3_P$3") (pintype "bidirectional"))
      (node (ref "R2") (pin "P$2") (pinfunction "2_P$2") (pintype "passive"))
      (node (ref "R3") (pin "P$2") (pinfunction "2_P$2") (pintype "passive"))
      (node (ref "U2") (pin "4") (pinfunction "VIN_4") (pintype "input"))
    )
    (net (code "126") (name "VDDIN") (class "Default")
      (node (ref "J3") (pin "P$2") (pinfunction "P$2_P$2") (pintype "bidirectional"))
      (node (ref "L1") (pin "1") (pinfunction "P$1_1") (pintype "bidirectional"))
    )
    (net (code "127") (name "XCIN") (class "Default")
      (node (ref "C19") (pin "P$1") (pinfunction "1_P$1") (pintype "passive"))
      (node (ref "U5") (pin "20") (pinfunction "XCIN_20") (pintype "bidirectional"))
      (node (ref "X2") (pin "P$1") (pinfunction "P$1_P$1") (pintype "bidirectional"))
    )
    (net (code "128") (name "XCOUT") (class "Default")
      (node (ref "C24") (pin "P$1") (pinfunction "1_P$1") (pintype "passive"))
      (node (ref "U5") (pin "21") (pinfunction "XCOUT_21") (pintype "bidirectional"))
      (node (ref "X2") (pin "P$2") (pinfunction "P$2_P$2") (pintype "bidirectional"))
    )
    (net (code "129") (name "XTAL1") (class "Default")
      (node (ref "C7") (pin "P$1") (pinfunction "1_P$1") (pintype "passive"))
      (node (ref "U5") (pin "23") (pinfunction "P2_13/XTAL_23") (pintype "bidirectional"))
      (node (ref "X1") (pin "1") (pinfunction "1_1") (pintype "bidirectional"))
    )
    (net (code "130") (name "XTAL2") (class "Default")
      (node (ref "C14") (pin "P$1") (pinfunction "1_P$1") (pintype "passive"))
      (node (ref "U5") (pin "24") (pinfunction "P2_12/EXTAL_24") (pintype "bidirectional"))
      (node (ref "X1") (pin "3") (pinfunction "3_3") (pintype "bidirectional"))
    )
    (net (code "131") (name "X_DIR") (class "Default")
      (node (ref "U5") (pin "118") (pinfunction "P6_4_118") (pintype "bidirectional"))
    )
    (net (code "132") (name "X_LS") (class "Default")
      (node (ref "U5") (pin "164") (pinfunction "P0_5/AN101_164") (pintype "bidirectional"))
    )
    (net (code "133") (name "X_STEP") (class "Default")
      (node (ref "U5") (pin "86") (pinfunction "P3_2_86") (pintype "bidirectional"))
    )
    (net (code "134") (name "Y_DIR") (class "Default")
      (node (ref "U5") (pin "115") (pinfunction "P6_7_115") (pintype "bidirectional"))
    )
    (net (code "135") (name "Y_LS") (class "Default")
      (node (ref "U5") (pin "175") (pinfunction "P5_12_175") (pintype "bidirectional"))
    )
    (net (code "136") (name "Y_STEP") (class "Default")
      (node (ref "U5") (pin "82") (pinfunction "P3_4_82") (pintype "bidirectional"))
    )
    (net (code "137") (name "Z_DIR") (class "Default")
      (node (ref "U5") (pin "121") (pinfunction "P6_1_121") (pintype "bidirectional"))
    )
    (net (code "138") (name "Z_LS") (class "Default")
      (node (ref "U5") (pin "169") (pinfunction "P0_0/AN0\\00_169") (pintype "bidirectional"))
    )
    (net (code "139") (name "Z_STEP") (class "Default")
      (node (ref "U5") (pin "92") (pinfunction "P1_11_92") (pintype "bidirectional"))
    )
    (net (code "140") (name "unconnected-(U5-P4_1-Pad2)") (class "Default")
      (node (ref "U5") (pin "2") (pinfunction "P4_1_2") (pintype "bidirectional"))
    )
    (net (code "141") (name "unconnected-(U5-P4_2-Pad3)") (class "Default")
      (node (ref "U5") (pin "3") (pinfunction "P4_2_3") (pintype "bidirectional"))
    )
    (net (code "142") (name "unconnected-(U5-P4_8-Pad43)") (class "Default")
      (node (ref "U5") (pin "43") (pinfunction "P4_8_43") (pintype "bidirectional"))
    )
    (net (code "143") (name "unconnected-(U5-P4_10-Pad41)") (class "Default")
      (node (ref "U5") (pin "41") (pinfunction "P4_10_41") (pintype "bidirectional"))
    )
    (net (code "144") (name "unconnected-(U5-P4_11-Pad40)") (class "Default")
      (node (ref "U5") (pin "40") (pinfunction "P4_11_40") (pintype "bidirectional"))
    )
    (net (code "145") (name "unconnected-(U5-P4_12-Pad39)") (class "Default")
      (node (ref "U5") (pin "39") (pinfunction "P4_12_39") (pintype "bidirectional"))
    )
    (net (code "146") (name "unconnected-(U5-P4_13-Pad38)") (class "Default")
      (node (ref "U5") (pin "38") (pinfunction "P4_13_38") (pintype "bidirectional"))
    )
    (net (code "147") (name "unconnected-(U5-P4_14-Pad37)") (class "Default")
      (node (ref "U5") (pin "37") (pinfunction "P4_14_37") (pintype "bidirectional"))
    )
    (net (code "148") (name "unconnected-(U5-P4_15-Pad36)") (class "Default")
      (node (ref "U5") (pin "36") (pinfunction "P4_15_36") (pintype "bidirectional"))
    )
    (net (code "149") (name "unconnected-(U5-P7_6-Pad14)") (class "Default")
      (node (ref "U5") (pin "14") (pinfunction "P7_6_14") (pintype "bidirectional"))
    )
    (net (code "150") (name "unconnected-(U5-P7_7-Pad15)") (class "Default")
      (node (ref "U5") (pin "15") (pinfunction "P7_7_15") (pintype "bidirectional"))
    )
    (net (code "151") (name "unconnected-(U5-PB_0-Pad16)") (class "Default")
      (node (ref "U5") (pin "16") (pinfunction "PB_0_16") (pintype "bidirectional"))
    )
    (net (code "152") (name "unconnected-(U5-VBAT-Pad18)") (class "Default")
      (node (ref "U5") (pin "18") (pinfunction "VBAT_18") (pintype "bidirectional"))
    )
    (net (code "153") (name "unconnected-(U5-VREFH-Pad154)") (class "Default")
      (node (ref "U5") (pin "154") (pinfunction "VREFH_154") (pintype "bidirectional"))
    )
    (net (code "154") (name "unconnected-(U5-VREFH0-Pad158)") (class "Default")
      (node (ref "U5") (pin "158") (pinfunction "VREFH0_158") (pintype "bidirectional"))
    )
    (net (code "155") (name "unconnected-(U5-VREFL-Pad153)") (class "Default")
      (node (ref "U5") (pin "153") (pinfunction "VREFL_153") (pintype "bidirectional"))
    )
    (net (code "156") (name "unconnected-(U5-VREFL0-Pad157)") (class "Default")
      (node (ref "U5") (pin "157") (pinfunction "VREFL0_157") (pintype "bidirectional"))
    )
  )
)
